# logger.net
KiCad netlist of a schematic drawn in EAGLE
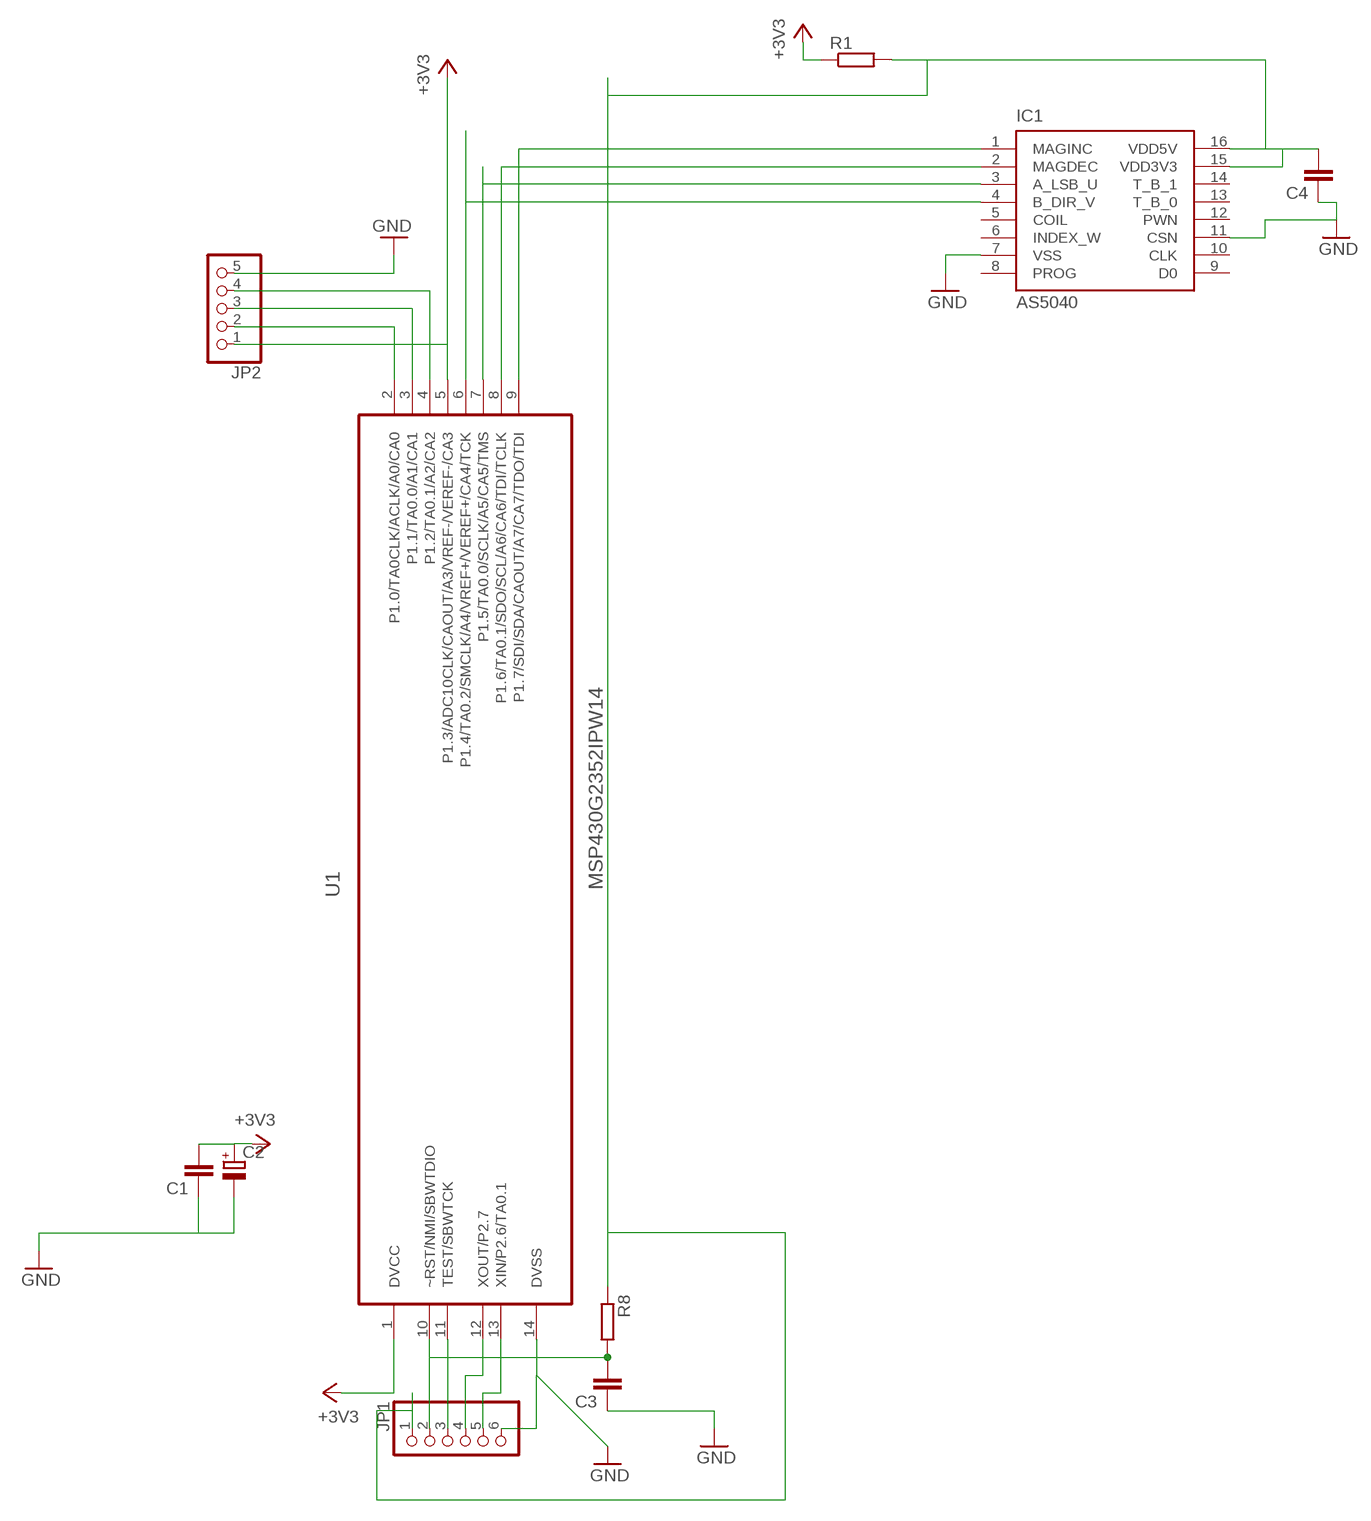
[diagram p0: schematic, sheet 1]

(export (version "E")
  (design (tool "Eeschema 10.0.6"))
  (components
    (comp (ref "C1")
      (value "C-EUC0805")
      (footprint "eagle-import:C0805")
      (libsource (lib "eagle-import") (part "C-EUC0805"))
    )
    (comp (ref "C2")
      (value "CPOL-EUE2,5-6E")
      (footprint "eagle-import:E2,5-6E")
      (libsource (lib "eagle-import") (part "CPOL-EUE2,5-6E"))
    )
    (comp (ref "C3")
      (value "C-EUC0805")
      (footprint "eagle-import:C0805")
      (libsource (lib "eagle-import") (part "C-EUC0805"))
    )
    (comp (ref "C4")
      (value "C-EUC0805")
      (footprint "eagle-import:C0805")
      (libsource (lib "eagle-import") (part "C-EUC0805"))
    )
    (comp (ref "IC1")
      (value "AS5040")
      (footprint "eagle-import:SSOP16")
      (fields (field (name "MPN") "AS5040ASSU"))
      (libsource (lib "eagle-import") (part "AS5040"))
    )
    (comp (ref "JP1")
      (value "PINHD-1X6/90")
      (footprint "eagle-import:1X06_90")
      (libsource (lib "eagle-import") (part "PINHD-1X6/90"))
    )
    (comp (ref "JP2")
      (value "PINHD-1X5/90")
      (footprint "eagle-import:1X05_90")
      (libsource (lib "eagle-import") (part "PINHD-1X5/90"))
    )
    (comp (ref "R1")
      (value "R-EU_R1206")
      (footprint "eagle-import:R1206")
      (libsource (lib "eagle-import") (part "R-EU_R1206"))
    )
    (comp (ref "R8")
      (value "R-EU_R0805")
      (footprint "eagle-import:R0805")
      (libsource (lib "eagle-import") (part "R-EU_R0805"))
    )
    (comp (ref "U1")
      (value "MSP430G2352IPW14")
      (footprint "eagle-import:SOP65P640X120-14N")
      (libsource (lib "eagle-import") (part "MSP430G2352IPW14"))
    )
  )
  (nets
    (net (code "1") (name "+3V3") (class "Default")
      (node (ref "C1") (pin "2") (pinfunction "2_2") (pintype "passive"))
      (node (ref "C2") (pin "+") (pinfunction "+_+") (pintype "passive"))
      (node (ref "JP2") (pin "1") (pinfunction "1_1") (pintype "passive"))
      (node (ref "R1") (pin "1") (pinfunction "1_1") (pintype "passive"))
      (node (ref "U1") (pin "1") (pinfunction "DVCC_1") (pintype "power_in"))
      (node (ref "U1") (pin "5") (pinfunction "P1.3/ADC10CLK/CAOUT/A3/VREF-/VEREF-/CA3_5") (pintype "bidirectional"))
    )
    (net (code "2") (name "GND") (class "Default")
      (node (ref "C1") (pin "1") (pinfunction "1_1") (pintype "passive"))
      (node (ref "C2") (pin "-") (pinfunction "-_-") (pintype "passive"))
      (node (ref "C3") (pin "1") (pinfunction "1_1") (pintype "passive"))
      (node (ref "C4") (pin "1") (pinfunction "1_1") (pintype "passive"))
      (node (ref "IC1") (pin "11") (pinfunction "CSN_11") (pintype "input"))
      (node (ref "IC1") (pin "7") (pinfunction "VSS_7") (pintype "passive"))
      (node (ref "JP1") (pin "6") (pinfunction "6_6") (pintype "passive"))
      (node (ref "JP2") (pin "5") (pinfunction "5_5") (pintype "passive"))
      (node (ref "U1") (pin "14") (pinfunction "DVSS_14") (pintype "power_in"))
    )
    (net (code "3") (name "Net-(IC1-A_LSB_U)") (class "Default")
      (node (ref "IC1") (pin "3") (pinfunction "A_LSB_U_3") (pintype "output"))
      (node (ref "U1") (pin "7") (pinfunction "P1.5/TA0.0/SCLK/A5/CA5/TMS_7") (pintype "bidirectional"))
    )
    (net (code "4") (name "Net-(IC1-B_DIR_V)") (class "Default")
      (node (ref "IC1") (pin "4") (pinfunction "B_DIR_V_4") (pintype "output"))
      (node (ref "U1") (pin "6") (pinfunction "P1.4/TA0.2/SMCLK/A4/VREF+/VEREF+/CA4/TCK_6") (pintype "bidirectional"))
    )
    (net (code "5") (name "Net-(IC1-MAGDEC)") (class "Default")
      (node (ref "IC1") (pin "2") (pinfunction "MAGDEC_2") (pintype "tri_state"))
      (node (ref "U1") (pin "8") (pinfunction "P1.6/TA0.1/SDO/SCL/A6/CA6/TDI/TCLK_8") (pintype "bidirectional"))
    )
    (net (code "6") (name "Net-(IC1-MAGINC)") (class "Default")
      (node (ref "IC1") (pin "1") (pinfunction "MAGINC_1") (pintype "tri_state"))
      (node (ref "U1") (pin "9") (pinfunction "P1.7/SDI/SDA/CAOUT/A7/CA7/TDO/TDI_9") (pintype "bidirectional"))
    )
    (net (code "7") (name "Net-(IC1-VDD3V3)") (class "Default")
      (node (ref "C4") (pin "2") (pinfunction "2_2") (pintype "passive"))
      (node (ref "IC1") (pin "15") (pinfunction "VDD3V3_15") (pintype "passive"))
      (node (ref "IC1") (pin "16") (pinfunction "VDD5V_16") (pintype "passive"))
      (node (ref "JP1") (pin "1") (pinfunction "1_1") (pintype "passive"))
      (node (ref "R1") (pin "2") (pinfunction "2_2") (pintype "passive"))
      (node (ref "R8") (pin "1") (pinfunction "1_1") (pintype "passive"))
    )
    (net (code "8") (name "Net-(U1-P1.0{slash}TA0CLK{slash}ACLK{slash}A0{slash}CA0)") (class "Default")
      (node (ref "JP2") (pin "2") (pinfunction "2_2") (pintype "passive"))
      (node (ref "U1") (pin "2") (pinfunction "P1.0/TA0CLK/ACLK/A0/CA0_2") (pintype "bidirectional"))
    )
    (net (code "9") (name "Net-(U1-P1.1{slash}TA0.0{slash}A1{slash}CA1)") (class "Default")
      (node (ref "JP2") (pin "3") (pinfunction "3_3") (pintype "passive"))
      (node (ref "U1") (pin "3") (pinfunction "P1.1/TA0.0/A1/CA1_3") (pintype "bidirectional"))
    )
    (net (code "10") (name "Net-(U1-P1.2{slash}TA0.1{slash}A2{slash}CA2)") (class "Default")
      (node (ref "JP2") (pin "4") (pinfunction "4_4") (pintype "passive"))
      (node (ref "U1") (pin "4") (pinfunction "P1.2/TA0.1/A2/CA2_4") (pintype "bidirectional"))
    )
    (net (code "11") (name "Net-(U1-TEST{slash}SBWTCK)") (class "Default")
      (node (ref "JP1") (pin "3") (pinfunction "3_3") (pintype "passive"))
      (node (ref "U1") (pin "11") (pinfunction "TEST/SBWTCK_11") (pintype "input"))
    )
    (net (code "12") (name "Net-(U1-XIN{slash}P2.6{slash}TA0.1)") (class "Default")
      (node (ref "JP1") (pin "5") (pinfunction "5_5") (pintype "passive"))
      (node (ref "U1") (pin "13") (pinfunction "XIN/P2.6/TA0.1_13") (pintype "bidirectional"))
    )
    (net (code "13") (name "Net-(U1-XOUT{slash}P2.7)") (class "Default")
      (node (ref "JP1") (pin "4") (pinfunction "4_4") (pintype "passive"))
      (node (ref "U1") (pin "12") (pinfunction "XOUT/P2.7_12") (pintype "bidirectional"))
    )
    (net (code "14") (name "Net-(U1-~{RST{slash}NMI{slash}SBWTDIO})") (class "Default")
      (node (ref "C3") (pin "2") (pinfunction "2_2") (pintype "passive"))
      (node (ref "JP1") (pin "2") (pinfunction "2_2") (pintype "passive"))
      (node (ref "R8") (pin "2") (pinfunction "2_2") (pintype "passive"))
      (node (ref "U1") (pin "10") (pinfunction "~{RST/NMI/SBWTDIO}_10") (pintype "input"))
    )
    (net (code "15") (name "unconnected-(IC1-CLK-Pad10)") (class "Default")
      (node (ref "IC1") (pin "10") (pinfunction "CLK_10") (pintype "input"))
    )
    (net (code "16") (name "unconnected-(IC1-COIL-Pad5)") (class "Default")
      (node (ref "IC1") (pin "5") (pinfunction "COIL_5") (pintype "no_connect"))
    )
    (net (code "17") (name "unconnected-(IC1-D0-Pad9)") (class "Default")
      (node (ref "IC1") (pin "9") (pinfunction "D0_9") (pintype "tri_state"))
    )
    (net (code "18") (name "unconnected-(IC1-INDEX_W-Pad6)") (class "Default")
      (node (ref "IC1") (pin "6") (pinfunction "INDEX_W_6") (pintype "output"))
    )
    (net (code "19") (name "unconnected-(IC1-PROG-Pad8)") (class "Default")
      (node (ref "IC1") (pin "8") (pinfunction "PROG_8") (pintype "input"))
    )
    (net (code "20") (name "unconnected-(IC1-PWN-Pad12)") (class "Default")
      (node (ref "IC1") (pin "12") (pinfunction "PWN_12") (pintype "passive"))
    )
    (net (code "21") (name "unconnected-(IC1-T_B_0-Pad13)") (class "Default")
      (node (ref "IC1") (pin "13") (pinfunction "T_B_0_13") (pintype "no_connect"))
    )
    (net (code "22") (name "unconnected-(IC1-T_B_1-Pad14)") (class "Default")
      (node (ref "IC1") (pin "14") (pinfunction "T_B_1_14") (pintype "no_connect"))
    )
  )
)
